# IUWASH_PIPE_BATTERY.net
KiCad netlist of a schematic drawn in EAGLE
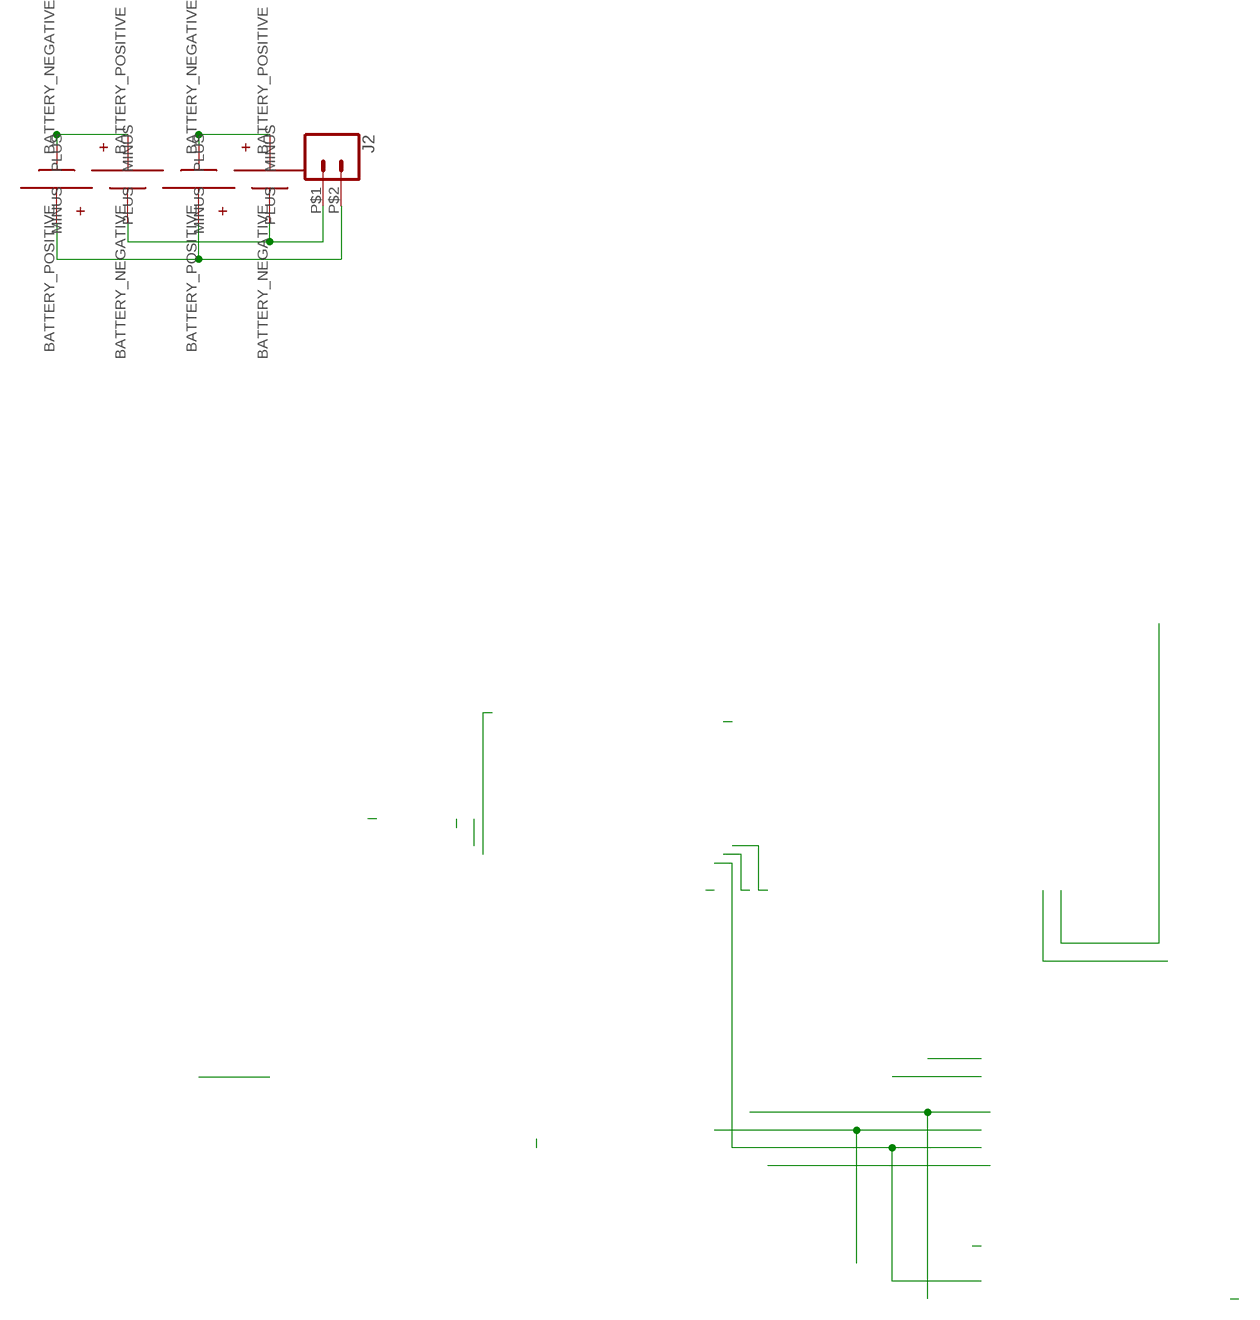
[diagram p0: schematic, sheet 1]

(export (version "E")
  (design (tool "Eeschema 10.0.6"))
  (components
    (comp (ref "J2")
      (value "CONN_02PTH2")
      (footprint "eagle-import:1X02_BIG")
      (libsource (lib "eagle-import") (part "CONN_02PTH2"))
    )
    (comp (ref "U$4")
      (value "SMT18650")
      (footprint "eagle-import:18650SMT")
      (libsource (lib "eagle-import") (part "SMT18650"))
    )
    (comp (ref "U$5")
      (value "SMT18650")
      (footprint "eagle-import:18650SMT")
      (libsource (lib "eagle-import") (part "SMT18650"))
    )
    (comp (ref "U$6")
      (value "SMT18650")
      (footprint "eagle-import:18650SMT")
      (libsource (lib "eagle-import") (part "SMT18650"))
    )
    (comp (ref "U$7")
      (value "SMT18650")
      (footprint "eagle-import:18650SMT")
      (libsource (lib "eagle-import") (part "SMT18650"))
    )
  )
  (nets
    (net (code "1") (name "Net-(J2-1)") (class "Default")
      (node (ref "J2") (pin "P$1") (pinfunction "1_P$1") (pintype "passive"))
      (node (ref "U$5") (pin "BATTERY_NEGATIVE") (pinfunction "MINUS_BATTERY_NEGATIVE") (pintype "bidirectional"))
      (node (ref "U$7") (pin "BATTERY_NEGATIVE") (pinfunction "MINUS_BATTERY_NEGATIVE") (pintype "bidirectional"))
    )
    (net (code "2") (name "Net-(J2-2)") (class "Default")
      (node (ref "J2") (pin "P$2") (pinfunction "2_P$2") (pintype "passive"))
      (node (ref "U$4") (pin "BATTERY_POSITIVE") (pinfunction "PLUS_BATTERY_POSITIVE") (pintype "bidirectional"))
      (node (ref "U$6") (pin "BATTERY_POSITIVE") (pinfunction "PLUS_BATTERY_POSITIVE") (pintype "bidirectional"))
    )
    (net (code "3") (name "Net-(U$4-MINUS)") (class "Default")
      (node (ref "U$4") (pin "BATTERY_NEGATIVE") (pinfunction "MINUS_BATTERY_NEGATIVE") (pintype "bidirectional"))
      (node (ref "U$5") (pin "BATTERY_POSITIVE") (pinfunction "PLUS_BATTERY_POSITIVE") (pintype "bidirectional"))
    )
    (net (code "4") (name "Net-(U$6-MINUS)") (class "Default")
      (node (ref "U$6") (pin "BATTERY_NEGATIVE") (pinfunction "MINUS_BATTERY_NEGATIVE") (pintype "bidirectional"))
      (node (ref "U$7") (pin "BATTERY_POSITIVE") (pinfunction "PLUS_BATTERY_POSITIVE") (pintype "bidirectional"))
    )
  )
)
